# Oscillatore_di_riferimento_intonazione.net
KiCad netlist of a schematic drawn in EAGLE
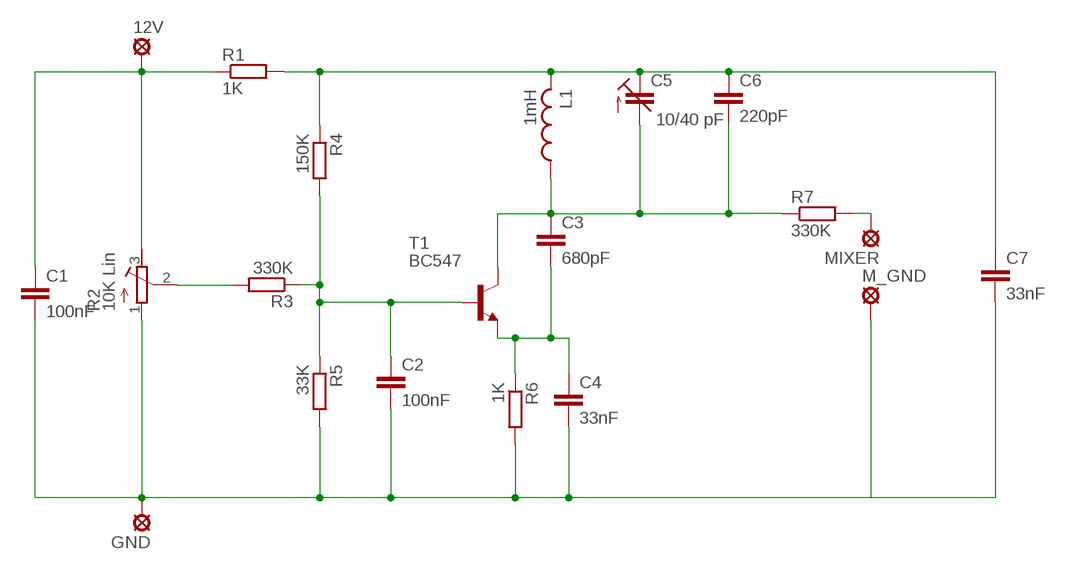
[diagram p0: schematic, sheet 1]

(export (version "E")
  (design (tool "Eeschema 10.0.6"))
  (components
    (comp (ref "12V")
      (value "LSP13")
      (footprint "eagle-import:LSP13")
      (libsource (lib "eagle-import") (part "LSP13"))
    )
    (comp (ref "C1")
      (value "100nF")
      (footprint "eagle-import:C7.5B3")
      (libsource (lib "eagle-import") (part "C7.5/3"))
    )
    (comp (ref "C2")
      (value "100nF")
      (footprint "eagle-import:C7.5B3")
      (libsource (lib "eagle-import") (part "C7.5/3"))
    )
    (comp (ref "C3")
      (value "680pF")
      (footprint "eagle-import:C7.5B3")
      (libsource (lib "eagle-import") (part "C7.5/3"))
    )
    (comp (ref "C4")
      (value "33nF")
      (footprint "eagle-import:C7.5B3")
      (libsource (lib "eagle-import") (part "C7.5/3"))
    )
    (comp (ref "C5")
      (value "10/40 pF")
      (footprint "eagle-import:3008")
      (libsource (lib "eagle-import") (part "C-TRIMM3008"))
    )
    (comp (ref "C6")
      (value "220pF")
      (footprint "eagle-import:C7.5B3")
      (libsource (lib "eagle-import") (part "C7.5/3"))
    )
    (comp (ref "C7")
      (value "33nF")
      (footprint "eagle-import:C7.5B3")
      (libsource (lib "eagle-import") (part "C7.5/3"))
    )
    (comp (ref "GND")
      (value "LSP13")
      (footprint "eagle-import:LSP13")
      (libsource (lib "eagle-import") (part "LSP13"))
    )
    (comp (ref "L1")
      (value "1mH")
      (footprint "eagle-import:0204_7")
      (libsource (lib "eagle-import") (part "L-US0204/7"))
    )
    (comp (ref "MIXER")
      (value "LSP13")
      (footprint "eagle-import:LSP13")
      (libsource (lib "eagle-import") (part "LSP13"))
    )
    (comp (ref "M_GND")
      (value "LSP13")
      (footprint "eagle-import:LSP13")
      (libsource (lib "eagle-import") (part "LSP13"))
    )
    (comp (ref "R1")
      (value "1K")
      (footprint "eagle-import:0207_10")
      (libsource (lib "eagle-import") (part "R-EU_0207/10"))
    )
    (comp (ref "R2")
      (value "10K Lin")
      (footprint "eagle-import:RTRIM3339P")
      (libsource (lib "eagle-import") (part "R-TRIMM3339P"))
    )
    (comp (ref "R3")
      (value "330K")
      (footprint "eagle-import:0207_10")
      (libsource (lib "eagle-import") (part "R-EU_0207/10"))
    )
    (comp (ref "R4")
      (value "150K")
      (footprint "eagle-import:0207_10")
      (libsource (lib "eagle-import") (part "R-EU_0207/10"))
    )
    (comp (ref "R5")
      (value "33K")
      (footprint "eagle-import:0207_10")
      (libsource (lib "eagle-import") (part "R-EU_0207/10"))
    )
    (comp (ref "R6")
      (value "1K")
      (footprint "eagle-import:0207_10")
      (libsource (lib "eagle-import") (part "R-EU_0207/10"))
    )
    (comp (ref "R7")
      (value "330K")
      (footprint "eagle-import:0207_10")
      (libsource (lib "eagle-import") (part "R-EU_0207/10"))
    )
    (comp (ref "T1")
      (value "BC547")
      (footprint "eagle-import:TO92")
      (libsource (lib "eagle-import") (part "BC547"))
    )
  )
  (nets
    (net (code "1") (name "Net-(C5-A)") (class "Default")
      (node (ref "C3") (pin "1") (pinfunction "1_1") (pintype "passive"))
      (node (ref "C5") (pin "-") (pinfunction "A_-") (pintype "passive"))
      (node (ref "C6") (pin "2") (pinfunction "2_2") (pintype "passive"))
      (node (ref "L1") (pin "1") (pinfunction "1_1") (pintype "passive"))
      (node (ref "R7") (pin "1") (pinfunction "1_1") (pintype "passive"))
      (node (ref "T1") (pin "3") (pinfunction "C_3") (pintype "passive"))
    )
    (net (code "2") (name "Net-(C5-E)") (class "Default")
      (node (ref "C5") (pin "+") (pinfunction "E_+") (pintype "passive"))
      (node (ref "C6") (pin "1") (pinfunction "1_1") (pintype "passive"))
      (node (ref "C7") (pin "1") (pinfunction "1_1") (pintype "passive"))
      (node (ref "L1") (pin "2") (pinfunction "2_2") (pintype "passive"))
      (node (ref "R1") (pin "2") (pinfunction "2_2") (pintype "passive"))
      (node (ref "R4") (pin "1") (pinfunction "1_1") (pintype "passive"))
    )
    (net (code "3") (name "Net-(MIXER-PadMP)") (class "Default")
      (node (ref "MIXER") (pin "MP") (pinfunction "MP_MP") (pintype "passive"))
      (node (ref "R7") (pin "2") (pinfunction "2_2") (pintype "passive"))
    )
    (net (code "4") (name "Net-(R2-A)") (class "Default")
      (node (ref "C1") (pin "2") (pinfunction "2_2") (pintype "passive"))
      (node (ref "C2") (pin "2") (pinfunction "2_2") (pintype "passive"))
      (node (ref "C4") (pin "2") (pinfunction "2_2") (pintype "passive"))
      (node (ref "C7") (pin "2") (pinfunction "2_2") (pintype "passive"))
      (node (ref "GND") (pin "MP") (pinfunction "MP_MP") (pintype "passive"))
      (node (ref "M_GND") (pin "MP") (pinfunction "MP_MP") (pintype "passive"))
      (node (ref "R2") (pin "1") (pinfunction "A_1") (pintype "passive"))
      (node (ref "R5") (pin "2") (pinfunction "2_2") (pintype "passive"))
      (node (ref "R6") (pin "2") (pinfunction "2_2") (pintype "passive"))
    )
    (net (code "5") (name "Net-(R2-E)") (class "Default")
      (node (ref "12V") (pin "MP") (pinfunction "MP_MP") (pintype "passive"))
      (node (ref "C1") (pin "1") (pinfunction "1_1") (pintype "passive"))
      (node (ref "R1") (pin "1") (pinfunction "1_1") (pintype "passive"))
      (node (ref "R2") (pin "3") (pinfunction "E_3") (pintype "passive"))
    )
    (net (code "6") (name "Net-(R2-S)") (class "Default")
      (node (ref "R2") (pin "2") (pinfunction "S_2") (pintype "passive"))
      (node (ref "R3") (pin "2") (pinfunction "2_2") (pintype "passive"))
    )
    (net (code "7") (name "Net-(T1-B)") (class "Default")
      (node (ref "C2") (pin "1") (pinfunction "1_1") (pintype "passive"))
      (node (ref "R3") (pin "1") (pinfunction "1_1") (pintype "passive"))
      (node (ref "R4") (pin "2") (pinfunction "2_2") (pintype "passive"))
      (node (ref "R5") (pin "1") (pinfunction "1_1") (pintype "passive"))
      (node (ref "T1") (pin "2") (pinfunction "B_2") (pintype "passive"))
    )
    (net (code "8") (name "Net-(T1-E)") (class "Default")
      (node (ref "C3") (pin "2") (pinfunction "2_2") (pintype "passive"))
      (node (ref "C4") (pin "1") (pinfunction "1_1") (pintype "passive"))
      (node (ref "R6") (pin "1") (pinfunction "1_1") (pintype "passive"))
      (node (ref "T1") (pin "1") (pinfunction "E_1") (pintype "passive"))
    )
  )
)
